# basic-inline-turbidimeter_main_board.net
KiCad netlist of a schematic drawn in EAGLE
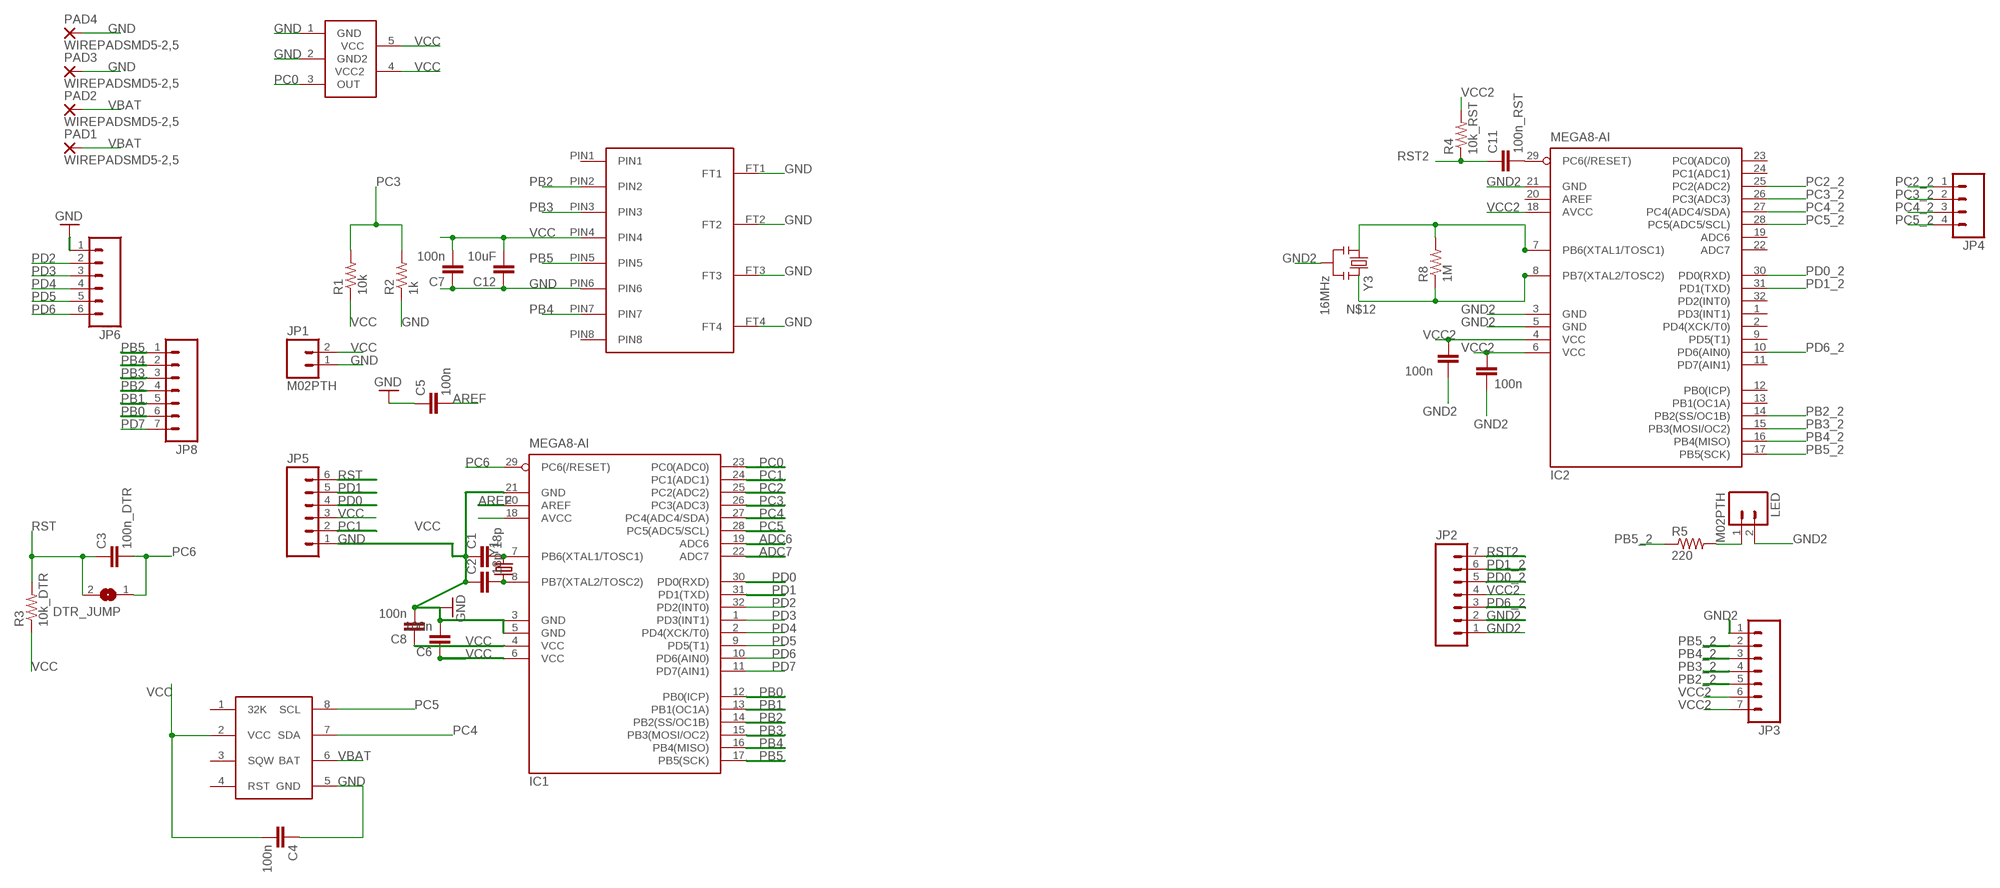
[diagram p0: schematic, sheet 1]

(export (version "E")
  (design (tool "Eeschema 10.0.6"))
  (components
    (comp (ref "*RTC")
      (value "DS3231M")
      (footprint "eagle-import:DS3231M")
      (libsource (lib "eagle-import") (part "DS3231M"))
    )
    (comp (ref "C1")
      (value "18p")
      (footprint "eagle-import:0603-CAP")
      (libsource (lib "eagle-import") (part "CAP0603-CAP"))
    )
    (comp (ref "C2")
      (value "18p")
      (footprint "eagle-import:0603-CAP")
      (libsource (lib "eagle-import") (part "CAP0603-CAP"))
    )
    (comp (ref "C3")
      (value "100n_DTR")
      (footprint "eagle-import:0603-CAP")
      (libsource (lib "eagle-import") (part "CAP0603-CAP"))
    )
    (comp (ref "C4")
      (value "100n")
      (footprint "eagle-import:0603-CAP")
      (libsource (lib "eagle-import") (part "CAP0603-CAP"))
    )
    (comp (ref "C5")
      (value "100n")
      (footprint "eagle-import:0603-CAP")
      (libsource (lib "eagle-import") (part "CAP0603-CAP"))
    )
    (comp (ref "C6")
      (value "100n")
      (footprint "eagle-import:0603-CAP")
      (libsource (lib "eagle-import") (part "CAP0603-CAP"))
    )
    (comp (ref "C7")
      (value "100n")
      (footprint "eagle-import:0603-CAP")
      (libsource (lib "eagle-import") (part "CAP0603-CAP"))
    )
    (comp (ref "C8")
      (value "100n")
      (footprint "eagle-import:0603-CAP")
      (libsource (lib "eagle-import") (part "CAP0603-CAP"))
    )
    (comp (ref "C9")
      (value "100n")
      (footprint "eagle-import:0603-CAP")
      (libsource (lib "eagle-import") (part "CAP0603-CAP"))
    )
    (comp (ref "C10")
      (value "100n")
      (footprint "eagle-import:0603-CAP")
      (libsource (lib "eagle-import") (part "CAP0603-CAP"))
    )
    (comp (ref "C11")
      (value "100n_RST")
      (footprint "eagle-import:0603-CAP")
      (libsource (lib "eagle-import") (part "CAP0603-CAP"))
    )
    (comp (ref "C12")
      (value "10uF")
      (footprint "eagle-import:0603-CAP")
      (libsource (lib "eagle-import") (part "CAP0603-CAP"))
    )
    (comp (ref "DTR_JUMP")
      (value "SJ")
      (footprint "eagle-import:SJ")
      (libsource (lib "eagle-import") (part "SJ"))
    )
    (comp (ref "IC1")
      (value "MEGA8-AI")
      (footprint "eagle-import:TQFP32-08")
      (fields (field (name "MPN") "ATMEGA8-16AU"))
      (libsource (lib "eagle-import") (part "MEGA8-AI"))
    )
    (comp (ref "IC2")
      (value "MEGA8-AI")
      (footprint "eagle-import:TQFP32-08")
      (fields (field (name "MPN") "ATMEGA8-16AU"))
      (libsource (lib "eagle-import") (part "MEGA8-AI"))
    )
    (comp (ref "JP1")
      (value "M02PTH")
      (footprint "eagle-import:1X02")
      (libsource (lib "eagle-import") (part "M02PTH"))
    )
    (comp (ref "JP2")
      (value "M07")
      (footprint "eagle-import:1X07")
      (libsource (lib "eagle-import") (part "M07"))
    )
    (comp (ref "JP3")
      (value "M07")
      (footprint "eagle-import:1X07")
      (libsource (lib "eagle-import") (part "M07"))
    )
    (comp (ref "JP4")
      (value "M04PTH")
      (footprint "eagle-import:1X04")
      (libsource (lib "eagle-import") (part "M04PTH"))
    )
    (comp (ref "JP5")
      (value "M06SIP")
      (footprint "eagle-import:1X06")
      (libsource (lib "eagle-import") (part "M06SIP"))
    )
    (comp (ref "JP6")
      (value "M06SIP")
      (footprint "eagle-import:1X06")
      (libsource (lib "eagle-import") (part "M06SIP"))
    )
    (comp (ref "JP8")
      (value "M07")
      (footprint "eagle-import:1X07")
      (libsource (lib "eagle-import") (part "M07"))
    )
    (comp (ref "LED")
      (value "M02PTH")
      (footprint "eagle-import:1X02")
      (libsource (lib "eagle-import") (part "M02PTH"))
    )
    (comp (ref "MICRO-SD")
      (value "MICROSD-1010030368")
      (footprint "eagle-import:MICROSD-1010030368")
      (libsource (lib "eagle-import") (part "MICROSD-1010030368"))
    )
    (comp (ref "PAD1")
      (value "WIREPADSMD5-2,5")
      (footprint "eagle-import:5-2,5")
      (libsource (lib "eagle-import") (part "WIREPADSMD5-2,5"))
    )
    (comp (ref "PAD2")
      (value "WIREPADSMD5-2,5")
      (footprint "eagle-import:5-2,5")
      (libsource (lib "eagle-import") (part "WIREPADSMD5-2,5"))
    )
    (comp (ref "PAD3")
      (value "WIREPADSMD5-2,5")
      (footprint "eagle-import:5-2,5")
      (libsource (lib "eagle-import") (part "WIREPADSMD5-2,5"))
    )
    (comp (ref "PAD4")
      (value "WIREPADSMD5-2,5")
      (footprint "eagle-import:5-2,5")
      (libsource (lib "eagle-import") (part "WIREPADSMD5-2,5"))
    )
    (comp (ref "R1")
      (value "10k")
      (footprint "eagle-import:0603-RES")
      (libsource (lib "eagle-import") (part "RESISTOR0603"))
    )
    (comp (ref "R2")
      (value "1k")
      (footprint "eagle-import:0603-RES")
      (libsource (lib "eagle-import") (part "RESISTOR0603"))
    )
    (comp (ref "R3")
      (value "10k_DTR")
      (footprint "eagle-import:0603-RES")
      (libsource (lib "eagle-import") (part "RESISTOR0603"))
    )
    (comp (ref "R4")
      (value "10k_RST")
      (footprint "eagle-import:0603-RES")
      (libsource (lib "eagle-import") (part "RESISTOR0603"))
    )
    (comp (ref "R5")
      (value "220")
      (footprint "eagle-import:0603-RES")
      (libsource (lib "eagle-import") (part "RESISTOR0603"))
    )
    (comp (ref "R8")
      (value "1M")
      (footprint "eagle-import:0603-RES")
      (libsource (lib "eagle-import") (part "RESISTOR0603"))
    )
    (comp (ref "U$4")
      (value "LMT86")
      (footprint "eagle-import:LMT86")
      (libsource (lib "eagle-import") (part "LMT86"))
    )
    (comp (ref "Y1")
      (value "CRYSTAL5X3")
      (footprint "eagle-import:CRYSTAL-SMD-5X3")
      (libsource (lib "eagle-import") (part "CRYSTAL5X3"))
    )
    (comp (ref "Y3")
      (value "16MHz")
      (footprint "eagle-import:RESONATOR-SMD")
      (libsource (lib "eagle-import") (part "RESONATOR16MHZ"))
    )
  )
  (nets
    (net (code "1") (name "/ADC6") (class "Default")
      (node (ref "IC1") (pin "19") (pinfunction "ADC6_19") (pintype "bidirectional"))
    )
    (net (code "2") (name "/ADC7") (class "Default")
      (node (ref "IC1") (pin "22") (pinfunction "ADC7_22") (pintype "bidirectional"))
    )
    (net (code "3") (name "/AREF") (class "Default")
      (node (ref "C5") (pin "2") (pinfunction "2_2") (pintype "passive"))
      (node (ref "IC1") (pin "20") (pinfunction "AREF_20") (pintype "passive"))
    )
    (net (code "4") (name "/GND2") (class "Default")
      (node (ref "C10") (pin "2") (pinfunction "2_2") (pintype "passive"))
      (node (ref "C9") (pin "2") (pinfunction "2_2") (pintype "passive"))
      (node (ref "IC2") (pin "21") (pinfunction "GND_21") (pintype "power_in"))
      (node (ref "IC2") (pin "3") (pinfunction "GND_3") (pintype "power_in"))
      (node (ref "IC2") (pin "5") (pinfunction "GND_5") (pintype "power_in"))
      (node (ref "JP2") (pin "1") (pinfunction "1_1") (pintype "passive"))
      (node (ref "JP2") (pin "2") (pinfunction "2_2") (pintype "passive"))
      (node (ref "JP3") (pin "1") (pinfunction "1_1") (pintype "passive"))
      (node (ref "LED") (pin "2") (pinfunction "2_2") (pintype "passive"))
      (node (ref "Y3") (pin "2") (pinfunction "2_2") (pintype "passive"))
    )
    (net (code "5") (name "/N$12") (class "Default")
      (node (ref "IC2") (pin "8") (pinfunction "PB7(XTAL2/TOSC2)_8") (pintype "bidirectional"))
      (node (ref "R8") (pin "1") (pinfunction "1_1") (pintype "passive"))
      (node (ref "Y3") (pin "3") (pinfunction "3_3") (pintype "passive"))
    )
    (net (code "6") (name "/PB0") (class "Default")
      (node (ref "IC1") (pin "12") (pinfunction "PB0(ICP)_12") (pintype "bidirectional"))
      (node (ref "JP8") (pin "6") (pinfunction "6_6") (pintype "passive"))
    )
    (net (code "7") (name "/PB1") (class "Default")
      (node (ref "IC1") (pin "13") (pinfunction "PB1(OC1A)_13") (pintype "bidirectional"))
      (node (ref "JP8") (pin "5") (pinfunction "5_5") (pintype "passive"))
    )
    (net (code "8") (name "/PB2") (class "Default")
      (node (ref "IC1") (pin "14") (pinfunction "PB2(SS/OC1B)_14") (pintype "bidirectional"))
      (node (ref "JP8") (pin "4") (pinfunction "4_4") (pintype "passive"))
      (node (ref "MICRO-SD") (pin "PIN2") (pinfunction "PIN2_PIN2") (pintype "bidirectional"))
    )
    (net (code "9") (name "/PB2_2") (class "Default")
      (node (ref "IC2") (pin "14") (pinfunction "PB2(SS/OC1B)_14") (pintype "bidirectional"))
      (node (ref "JP3") (pin "5") (pinfunction "5_5") (pintype "passive"))
    )
    (net (code "10") (name "/PB3") (class "Default")
      (node (ref "IC1") (pin "15") (pinfunction "PB3(MOSI/OC2)_15") (pintype "bidirectional"))
      (node (ref "JP8") (pin "3") (pinfunction "3_3") (pintype "passive"))
      (node (ref "MICRO-SD") (pin "PIN3") (pinfunction "PIN3_PIN3") (pintype "bidirectional"))
    )
    (net (code "11") (name "/PB3_2") (class "Default")
      (node (ref "IC2") (pin "15") (pinfunction "PB3(MOSI/OC2)_15") (pintype "bidirectional"))
      (node (ref "JP3") (pin "4") (pinfunction "4_4") (pintype "passive"))
    )
    (net (code "12") (name "/PB4") (class "Default")
      (node (ref "IC1") (pin "16") (pinfunction "PB4(MISO)_16") (pintype "bidirectional"))
      (node (ref "JP8") (pin "2") (pinfunction "2_2") (pintype "passive"))
      (node (ref "MICRO-SD") (pin "PIN7") (pinfunction "PIN7_PIN7") (pintype "bidirectional"))
    )
    (net (code "13") (name "/PB4_2") (class "Default")
      (node (ref "IC2") (pin "16") (pinfunction "PB4(MISO)_16") (pintype "bidirectional"))
      (node (ref "JP3") (pin "3") (pinfunction "3_3") (pintype "passive"))
    )
    (net (code "14") (name "/PB5") (class "Default")
      (node (ref "IC1") (pin "17") (pinfunction "PB5(SCK)_17") (pintype "bidirectional"))
      (node (ref "JP8") (pin "1") (pinfunction "1_1") (pintype "passive"))
      (node (ref "MICRO-SD") (pin "PIN5") (pinfunction "PIN5_PIN5") (pintype "bidirectional"))
    )
    (net (code "15") (name "/PB5_2") (class "Default")
      (node (ref "IC2") (pin "17") (pinfunction "PB5(SCK)_17") (pintype "bidirectional"))
      (node (ref "JP3") (pin "2") (pinfunction "2_2") (pintype "passive"))
      (node (ref "R5") (pin "1") (pinfunction "1_1") (pintype "passive"))
    )
    (net (code "16") (name "/PC0") (class "Default")
      (node (ref "IC1") (pin "23") (pinfunction "PC0(ADC0)_23") (pintype "bidirectional"))
      (node (ref "U$4") (pin "3") (pinfunction "OUT_3") (pintype "bidirectional"))
    )
    (net (code "17") (name "/PC1") (class "Default")
      (node (ref "IC1") (pin "24") (pinfunction "PC1(ADC1)_24") (pintype "bidirectional"))
      (node (ref "JP5") (pin "2") (pinfunction "2_2") (pintype "passive"))
    )
    (net (code "18") (name "/PC2") (class "Default")
      (node (ref "IC1") (pin "25") (pinfunction "PC2(ADC2)_25") (pintype "bidirectional"))
    )
    (net (code "19") (name "/PC2_2") (class "Default")
      (node (ref "IC2") (pin "25") (pinfunction "PC2(ADC2)_25") (pintype "bidirectional"))
      (node (ref "JP4") (pin "1") (pinfunction "1_1") (pintype "passive"))
    )
    (net (code "20") (name "/PC3") (class "Default")
      (node (ref "IC1") (pin "26") (pinfunction "PC3(ADC3)_26") (pintype "bidirectional"))
      (node (ref "R1") (pin "2") (pinfunction "2_2") (pintype "passive"))
      (node (ref "R2") (pin "2") (pinfunction "2_2") (pintype "passive"))
    )
    (net (code "21") (name "/PC3_2") (class "Default")
      (node (ref "IC2") (pin "26") (pinfunction "PC3(ADC3)_26") (pintype "bidirectional"))
      (node (ref "JP4") (pin "2") (pinfunction "2_2") (pintype "passive"))
    )
    (net (code "22") (name "/PC4") (class "Default")
      (node (ref "*RTC") (pin "7") (pinfunction "SDA_7") (pintype "bidirectional"))
      (node (ref "IC1") (pin "27") (pinfunction "PC4(ADC4/SDA)_27") (pintype "bidirectional"))
    )
    (net (code "23") (name "/PC4_2") (class "Default")
      (node (ref "IC2") (pin "27") (pinfunction "PC4(ADC4/SDA)_27") (pintype "bidirectional"))
      (node (ref "JP4") (pin "3") (pinfunction "3_3") (pintype "passive"))
    )
    (net (code "24") (name "/PC5") (class "Default")
      (node (ref "*RTC") (pin "8") (pinfunction "SCL_8") (pintype "bidirectional"))
      (node (ref "IC1") (pin "28") (pinfunction "PC5(ADC5/SCL)_28") (pintype "bidirectional"))
    )
    (net (code "25") (name "/PC5_2") (class "Default")
      (node (ref "IC2") (pin "28") (pinfunction "PC5(ADC5/SCL)_28") (pintype "bidirectional"))
      (node (ref "JP4") (pin "4") (pinfunction "4_4") (pintype "passive"))
    )
    (net (code "26") (name "/PC6") (class "Default")
      (node (ref "C3") (pin "2") (pinfunction "2_2") (pintype "passive"))
      (node (ref "DTR_JUMP") (pin "1") (pinfunction "1_1") (pintype "passive"))
      (node (ref "IC1") (pin "29") (pinfunction "PC6(/RESET)_29") (pintype "bidirectional"))
    )
    (net (code "27") (name "/PD0") (class "Default")
      (node (ref "IC1") (pin "30") (pinfunction "PD0(RXD)_30") (pintype "bidirectional"))
      (node (ref "JP5") (pin "4") (pinfunction "4_4") (pintype "passive"))
    )
    (net (code "28") (name "/PD0_2") (class "Default")
      (node (ref "IC2") (pin "30") (pinfunction "PD0(RXD)_30") (pintype "bidirectional"))
      (node (ref "JP2") (pin "5") (pinfunction "5_5") (pintype "passive"))
    )
    (net (code "29") (name "/PD1") (class "Default")
      (node (ref "IC1") (pin "31") (pinfunction "PD1(TXD)_31") (pintype "bidirectional"))
      (node (ref "JP5") (pin "5") (pinfunction "5_5") (pintype "passive"))
    )
    (net (code "30") (name "/PD1_2") (class "Default")
      (node (ref "IC2") (pin "31") (pinfunction "PD1(TXD)_31") (pintype "bidirectional"))
      (node (ref "JP2") (pin "6") (pinfunction "6_6") (pintype "passive"))
    )
    (net (code "31") (name "/PD2") (class "Default")
      (node (ref "IC1") (pin "32") (pinfunction "PD2(INT0)_32") (pintype "bidirectional"))
      (node (ref "JP6") (pin "2") (pinfunction "2_2") (pintype "passive"))
    )
    (net (code "32") (name "/PD3") (class "Default")
      (node (ref "IC1") (pin "1") (pinfunction "PD3(INT1)_1") (pintype "bidirectional"))
      (node (ref "JP6") (pin "3") (pinfunction "3_3") (pintype "passive"))
    )
    (net (code "33") (name "/PD4") (class "Default")
      (node (ref "IC1") (pin "2") (pinfunction "PD4(XCK/T0)_2") (pintype "bidirectional"))
      (node (ref "JP6") (pin "4") (pinfunction "4_4") (pintype "passive"))
    )
    (net (code "34") (name "/PD5") (class "Default")
      (node (ref "IC1") (pin "9") (pinfunction "PD5(T1)_9") (pintype "bidirectional"))
      (node (ref "JP6") (pin "5") (pinfunction "5_5") (pintype "passive"))
    )
    (net (code "35") (name "/PD6") (class "Default")
      (node (ref "IC1") (pin "10") (pinfunction "PD6(AIN0)_10") (pintype "bidirectional"))
      (node (ref "JP6") (pin "6") (pinfunction "6_6") (pintype "passive"))
    )
    (net (code "36") (name "/PD6_2") (class "Default")
      (node (ref "IC2") (pin "10") (pinfunction "PD6(AIN0)_10") (pintype "bidirectional"))
      (node (ref "JP2") (pin "3") (pinfunction "3_3") (pintype "passive"))
    )
    (net (code "37") (name "/PD7") (class "Default")
      (node (ref "IC1") (pin "11") (pinfunction "PD7(AIN1)_11") (pintype "bidirectional"))
      (node (ref "JP8") (pin "7") (pinfunction "7_7") (pintype "passive"))
    )
    (net (code "38") (name "/RST") (class "Default")
      (node (ref "C3") (pin "1") (pinfunction "1_1") (pintype "passive"))
      (node (ref "DTR_JUMP") (pin "2") (pinfunction "2_2") (pintype "passive"))
      (node (ref "JP5") (pin "6") (pinfunction "6_6") (pintype "passive"))
      (node (ref "R3") (pin "2") (pinfunction "2_2") (pintype "passive"))
    )
    (net (code "39") (name "/RST2") (class "Default")
      (node (ref "C11") (pin "1") (pinfunction "1_1") (pintype "passive"))
      (node (ref "JP2") (pin "7") (pinfunction "7_7") (pintype "passive"))
      (node (ref "R4") (pin "1") (pinfunction "1_1") (pintype "passive"))
    )
    (net (code "40") (name "/VBAT") (class "Default")
      (node (ref "*RTC") (pin "6") (pinfunction "BAT_6") (pintype "bidirectional"))
      (node (ref "PAD1") (pin "1") (pinfunction "P_1") (pintype "passive"))
      (node (ref "PAD2") (pin "1") (pinfunction "P_1") (pintype "passive"))
    )
    (net (code "41") (name "/VCC") (class "Default")
      (node (ref "*RTC") (pin "2") (pinfunction "VCC_2") (pintype "bidirectional"))
      (node (ref "C12") (pin "2") (pinfunction "2_2") (pintype "passive"))
      (node (ref "C4") (pin "2") (pinfunction "2_2") (pintype "passive"))
      (node (ref "C6") (pin "1") (pinfunction "1_1") (pintype "passive"))
      (node (ref "C7") (pin "2") (pinfunction "2_2") (pintype "passive"))
      (node (ref "C8") (pin "1") (pinfunction "1_1") (pintype "passive"))
      (node (ref "IC1") (pin "18") (pinfunction "AVCC_18") (pintype "power_in"))
      (node (ref "IC1") (pin "4") (pinfunction "VCC_4") (pintype "power_in"))
      (node (ref "IC1") (pin "6") (pinfunction "VCC_6") (pintype "power_in"))
      (node (ref "JP1") (pin "2") (pinfunction "2_2") (pintype "passive"))
      (node (ref "JP5") (pin "3") (pinfunction "3_3") (pintype "passive"))
      (node (ref "MICRO-SD") (pin "PIN4") (pinfunction "PIN4_PIN4") (pintype "bidirectional"))
      (node (ref "R1") (pin "1") (pinfunction "1_1") (pintype "passive"))
      (node (ref "R3") (pin "1") (pinfunction "1_1") (pintype "passive"))
      (node (ref "U$4") (pin "4") (pinfunction "VCC2_4") (pintype "bidirectional"))
      (node (ref "U$4") (pin "5") (pinfunction "VCC_5") (pintype "bidirectional"))
    )
    (net (code "42") (name "/VCC2") (class "Default")
      (node (ref "C10") (pin "1") (pinfunction "1_1") (pintype "passive"))
      (node (ref "C9") (pin "1") (pinfunction "1_1") (pintype "passive"))
      (node (ref "IC2") (pin "18") (pinfunction "AVCC_18") (pintype "power_in"))
      (node (ref "IC2") (pin "4") (pinfunction "VCC_4") (pintype "power_in"))
      (node (ref "IC2") (pin "6") (pinfunction "VCC_6") (pintype "power_in"))
      (node (ref "JP2") (pin "4") (pinfunction "4_4") (pintype "passive"))
      (node (ref "JP3") (pin "6") (pinfunction "6_6") (pintype "passive"))
      (node (ref "JP3") (pin "7") (pinfunction "7_7") (pintype "passive"))
      (node (ref "R4") (pin "2") (pinfunction "2_2") (pintype "passive"))
    )
    (net (code "43") (name "GND") (class "Default")
      (node (ref "*RTC") (pin "5") (pinfunction "GND_5") (pintype "bidirectional"))
      (node (ref "C1") (pin "1") (pinfunction "1_1") (pintype "passive"))
      (node (ref "C12") (pin "1") (pinfunction "1_1") (pintype "passive"))
      (node (ref "C2") (pin "1") (pinfunction "1_1") (pintype "passive"))
      (node (ref "C4") (pin "1") (pinfunction "1_1") (pintype "passive"))
      (node (ref "C5") (pin "1") (pinfunction "1_1") (pintype "passive"))
      (node (ref "C6") (pin "2") (pinfunction "2_2") (pintype "passive"))
      (node (ref "C7") (pin "1") (pinfunction "1_1") (pintype "passive"))
      (node (ref "C8") (pin "2") (pinfunction "2_2") (pintype "passive"))
      (node (ref "IC1") (pin "21") (pinfunction "GND_21") (pintype "power_in"))
      (node (ref "IC1") (pin "3") (pinfunction "GND_3") (pintype "power_in"))
      (node (ref "IC1") (pin "5") (pinfunction "GND_5") (pintype "power_in"))
      (node (ref "JP1") (pin "1") (pinfunction "1_1") (pintype "passive"))
      (node (ref "JP5") (pin "1") (pinfunction "1_1") (pintype "passive"))
      (node (ref "JP6") (pin "1") (pinfunction "1_1") (pintype "passive"))
      (node (ref "MICRO-SD") (pin "FT1") (pinfunction "FT1_FT1") (pintype "bidirectional"))
      (node (ref "MICRO-SD") (pin "FT2") (pinfunction "FT2_FT2") (pintype "bidirectional"))
      (node (ref "MICRO-SD") (pin "FT3") (pinfunction "FT3_FT3") (pintype "bidirectional"))
      (node (ref "MICRO-SD") (pin "FT4") (pinfunction "FT4_FT4") (pintype "bidirectional"))
      (node (ref "MICRO-SD") (pin "PIN6") (pinfunction "PIN6_PIN6") (pintype "bidirectional"))
      (node (ref "PAD3") (pin "1") (pinfunction "P_1") (pintype "passive"))
      (node (ref "PAD4") (pin "1") (pinfunction "P_1") (pintype "passive"))
      (node (ref "R2") (pin "1") (pinfunction "1_1") (pintype "passive"))
      (node (ref "U$4") (pin "1") (pinfunction "GND_1") (pintype "bidirectional"))
      (node (ref "U$4") (pin "2") (pinfunction "GND2_2") (pintype "bidirectional"))
    )
    (net (code "44") (name "Net-(IC1-PB6(XTAL1{slash}TOSC1))") (class "Default")
      (node (ref "C1") (pin "2") (pinfunction "2_2") (pintype "passive"))
      (node (ref "IC1") (pin "7") (pinfunction "PB6(XTAL1/TOSC1)_7") (pintype "bidirectional"))
      (node (ref "Y1") (pin "3") (pinfunction "2_3") (pintype "passive"))
    )
    (net (code "45") (name "Net-(IC1-PB7(XTAL2{slash}TOSC2))") (class "Default")
      (node (ref "C2") (pin "2") (pinfunction "2_2") (pintype "passive"))
      (node (ref "IC1") (pin "8") (pinfunction "PB7(XTAL2/TOSC2)_8") (pintype "bidirectional"))
      (node (ref "Y1") (pin "1") (pinfunction "1_1") (pintype "passive"))
    )
    (net (code "46") (name "Net-(IC2-PB6(XTAL1{slash}TOSC1))") (class "Default")
      (node (ref "IC2") (pin "7") (pinfunction "PB6(XTAL1/TOSC1)_7") (pintype "bidirectional"))
      (node (ref "R8") (pin "2") (pinfunction "2_2") (pintype "passive"))
      (node (ref "Y3") (pin "1") (pinfunction "1_1") (pintype "passive"))
    )
    (net (code "47") (name "Net-(IC2-PC6({slash}RESET))") (class "Default")
      (node (ref "C11") (pin "2") (pinfunction "2_2") (pintype "passive"))
      (node (ref "IC2") (pin "29") (pinfunction "PC6(/RESET)_29") (pintype "bidirectional"))
    )
    (net (code "48") (name "Net-(LED-Pad1)") (class "Default")
      (node (ref "LED") (pin "1") (pinfunction "1_1") (pintype "passive"))
      (node (ref "R5") (pin "2") (pinfunction "2_2") (pintype "passive"))
    )
    (net (code "49") (name "unconnected-(*RTC-32K-Pad1)") (class "Default")
      (node (ref "*RTC") (pin "1") (pinfunction "32K_1") (pintype "bidirectional"))
    )
    (net (code "50") (name "unconnected-(*RTC-RST-Pad4)") (class "Default")
      (node (ref "*RTC") (pin "4") (pinfunction "RST_4") (pintype "bidirectional"))
    )
    (net (code "51") (name "unconnected-(*RTC-SQW-Pad3)") (class "Default")
      (node (ref "*RTC") (pin "3") (pinfunction "SQW_3") (pintype "bidirectional"))
    )
    (net (code "52") (name "unconnected-(IC2-ADC6-Pad19)") (class "Default")
      (node (ref "IC2") (pin "19") (pinfunction "ADC6_19") (pintype "bidirectional"))
    )
    (net (code "53") (name "unconnected-(IC2-ADC7-Pad22)") (class "Default")
      (node (ref "IC2") (pin "22") (pinfunction "ADC7_22") (pintype "bidirectional"))
    )
    (net (code "54") (name "unconnected-(IC2-AREF-Pad20)") (class "Default")
      (node (ref "IC2") (pin "20") (pinfunction "AREF_20") (pintype "passive"))
    )
    (net (code "55") (name "unconnected-(IC2-PB0(ICP)-Pad12)") (class "Default")
      (node (ref "IC2") (pin "12") (pinfunction "PB0(ICP)_12") (pintype "bidirectional"))
    )
    (net (code "56") (name "unconnected-(IC2-PB1(OC1A)-Pad13)") (class "Default")
      (node (ref "IC2") (pin "13") (pinfunction "PB1(OC1A)_13") (pintype "bidirectional"))
    )
    (net (code "57") (name "unconnected-(IC2-PC0(ADC0)-Pad23)") (class "Default")
      (node (ref "IC2") (pin "23") (pinfunction "PC0(ADC0)_23") (pintype "bidirectional"))
    )
    (net (code "58") (name "unconnected-(IC2-PC1(ADC1)-Pad24)") (class "Default")
      (node (ref "IC2") (pin "24") (pinfunction "PC1(ADC1)_24") (pintype "bidirectional"))
    )
    (net (code "59") (name "unconnected-(IC2-PD2(INT0)-Pad32)") (class "Default")
      (node (ref "IC2") (pin "32") (pinfunction "PD2(INT0)_32") (pintype "bidirectional"))
    )
    (net (code "60") (name "unconnected-(IC2-PD3(INT1)-Pad1)") (class "Default")
      (node (ref "IC2") (pin "1") (pinfunction "PD3(INT1)_1") (pintype "bidirectional"))
    )
    (net (code "61") (name "unconnected-(IC2-PD4(XCK{slash}T0)-Pad2)") (class "Default")
      (node (ref "IC2") (pin "2") (pinfunction "PD4(XCK/T0)_2") (pintype "bidirectional"))
    )
    (net (code "62") (name "unconnected-(IC2-PD5(T1)-Pad9)") (class "Default")
      (node (ref "IC2") (pin "9") (pinfunction "PD5(T1)_9") (pintype "bidirectional"))
    )
    (net (code "63") (name "unconnected-(IC2-PD7(AIN1)-Pad11)") (class "Default")
      (node (ref "IC2") (pin "11") (pinfunction "PD7(AIN1)_11") (pintype "bidirectional"))
    )
    (net (code "64") (name "unconnected-(MICRO-SD-PadPIN1)") (class "Default")
      (node (ref "MICRO-SD") (pin "PIN1") (pinfunction "PIN1_PIN1") (pintype "bidirectional"))
    )
    (net (code "65") (name "unconnected-(MICRO-SD-PadPIN8)") (class "Default")
      (node (ref "MICRO-SD") (pin "PIN8") (pinfunction "PIN8_PIN8") (pintype "bidirectional"))
    )
  )
)
